# Adafruit_FTDI_Friend_Rev_B.net
KiCad netlist of a schematic drawn in EAGLE
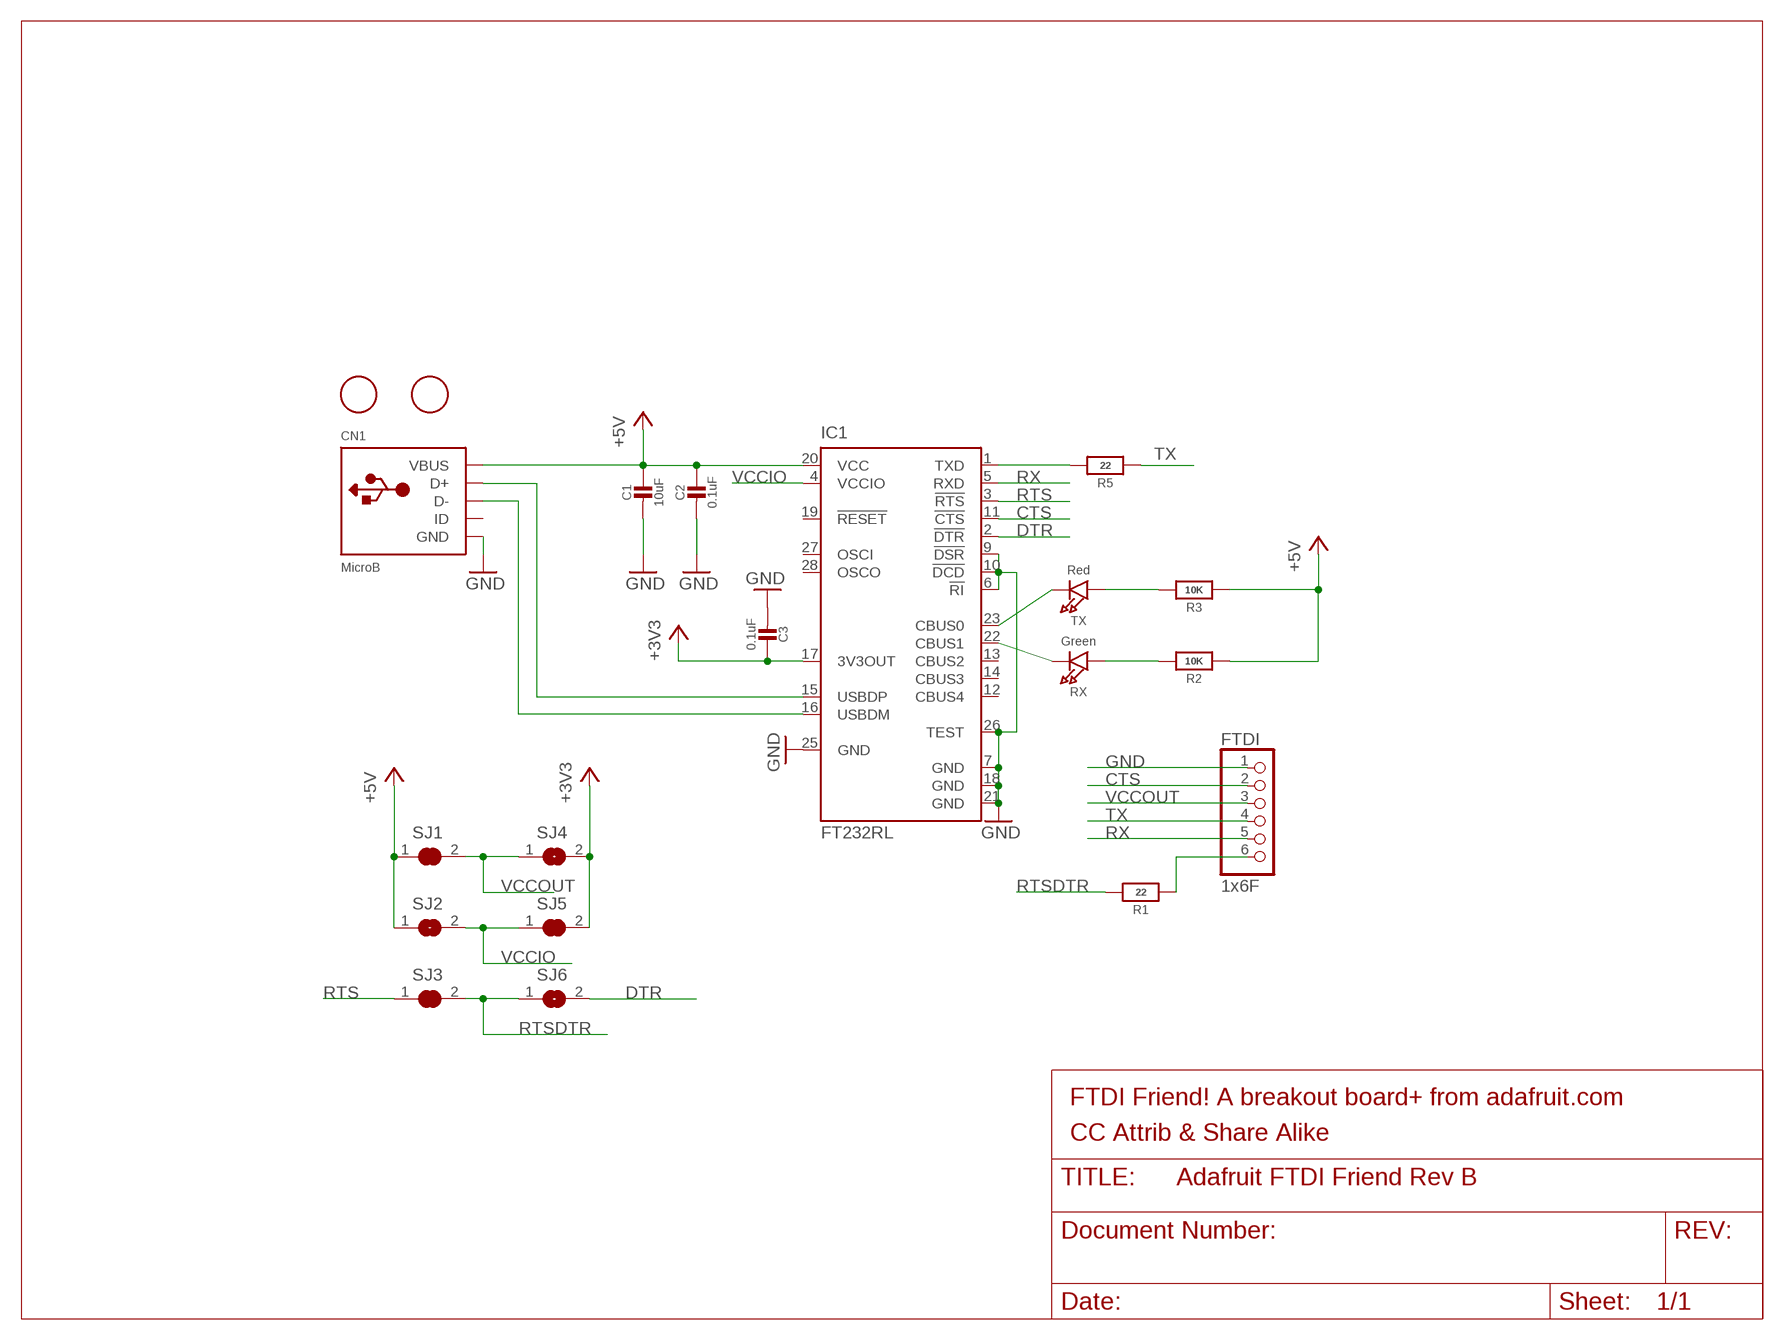
[diagram p0: schematic, sheet 1]

(export (version "E")
  (design (tool "Eeschema 10.0.6"))
  (components
    (comp (ref "C1")
      (value "10uF")
      (footprint "eagle-import:0805-NO")
      (libsource (lib "eagle-import") (part "CAP_CERAMIC0805-NOOUTLINE"))
    )
    (comp (ref "C2")
      (value "0.1uF")
      (footprint "eagle-import:0603-NO")
      (libsource (lib "eagle-import") (part "CAP_CERAMIC0603_NO"))
    )
    (comp (ref "C3")
      (value "0.1uF")
      (footprint "eagle-import:0603-NO")
      (libsource (lib "eagle-import") (part "CAP_CERAMIC0603_NO"))
    )
    (comp (ref "CN1")
      (value "MicroB")
      (footprint "eagle-import:SHOU_MICROXNJ073")
      (libsource (lib "eagle-import") (part "USB_MICROXNJ073"))
    )
    (comp (ref "FTDI")
      (value "1x6F")
      (footprint "eagle-import:1X06-CLEANBIG")
      (libsource (lib "eagle-import") (part "PINHD-1X6CB"))
    )
    (comp (ref "IC1")
      (value "FT232RL")
      (footprint "eagle-import:SSOP28")
      (libsource (lib "eagle-import") (part "FT232RL"))
    )
    (comp (ref "R1")
      (value "22")
      (footprint "eagle-import:0603-NO")
      (libsource (lib "eagle-import") (part "RESISTOR_0603_NOOUT"))
    )
    (comp (ref "R2")
      (value "10K")
      (footprint "eagle-import:0603-NO")
      (libsource (lib "eagle-import") (part "RESISTOR_0603_NOOUT"))
    )
    (comp (ref "R3")
      (value "10K")
      (footprint "eagle-import:0603-NO")
      (libsource (lib "eagle-import") (part "RESISTOR_0603_NOOUT"))
    )
    (comp (ref "R5")
      (value "22")
      (footprint "eagle-import:0603-NO")
      (libsource (lib "eagle-import") (part "RESISTOR_0603_NOOUT"))
    )
    (comp (ref "RX")
      (value "Green")
      (footprint "eagle-import:CHIPLED_0603_NOOUTLINE")
      (libsource (lib "eagle-import") (part "LED0603_NOOUTLINE"))
    )
    (comp (ref "SJ1")
      (value "SOLDERJUMPER_CLOSED")
      (footprint "eagle-import:SOLDERJUMPER_CLOSEDWIRE")
      (libsource (lib "eagle-import") (part "SOLDERJUMPER_CLOSED"))
    )
    (comp (ref "SJ2")
      (value "SOLDERJUMPER")
      (footprint "eagle-import:SOLDERJUMPER_ARROW_NOPASTE")
      (libsource (lib "eagle-import") (part "SOLDERJUMPER"))
    )
    (comp (ref "SJ3")
      (value "SOLDERJUMPER_CLOSED")
      (footprint "eagle-import:SOLDERJUMPER_CLOSEDWIRE")
      (libsource (lib "eagle-import") (part "SOLDERJUMPER_CLOSED"))
    )
    (comp (ref "SJ4")
      (value "SOLDERJUMPER")
      (footprint "eagle-import:SOLDERJUMPER_ARROW_NOPASTE")
      (libsource (lib "eagle-import") (part "SOLDERJUMPER"))
    )
    (comp (ref "SJ5")
      (value "SOLDERJUMPER_CLOSED")
      (footprint "eagle-import:SOLDERJUMPER_CLOSEDWIRE")
      (libsource (lib "eagle-import") (part "SOLDERJUMPER_CLOSED"))
    )
    (comp (ref "SJ6")
      (value "SOLDERJUMPER")
      (footprint "eagle-import:SOLDERJUMPER_ARROW_NOPASTE")
      (libsource (lib "eagle-import") (part "SOLDERJUMPER"))
    )
    (comp (ref "TX")
      (value "Red")
      (footprint "eagle-import:CHIPLED_0603_NOOUTLINE")
      (libsource (lib "eagle-import") (part "LED0603_NOOUTLINE"))
    )
    (comp (ref "U$1")
      (value "FIDUCIAL")
      (footprint "eagle-import:FIDUCIAL_1MM")
      (libsource (lib "eagle-import") (part "FIDUCIAL"))
    )
    (comp (ref "U$2")
      (value "FIDUCIAL")
      (footprint "eagle-import:FIDUCIAL_1MM")
      (libsource (lib "eagle-import") (part "FIDUCIAL"))
    )
  )
  (nets
    (net (code "1") (name "+3V3") (class "Default")
      (node (ref "C3") (pin "1") (pinfunction "1_1") (pintype "passive"))
      (node (ref "IC1") (pin "17") (pinfunction "3V3OUT_17") (pintype "output"))
      (node (ref "SJ4") (pin "2") (pinfunction "2_2") (pintype "passive"))
      (node (ref "SJ5") (pin "2") (pinfunction "2_2") (pintype "passive"))
    )
    (net (code "2") (name "+5V") (class "Default")
      (node (ref "C1") (pin "1") (pinfunction "1_1") (pintype "passive"))
      (node (ref "C2") (pin "1") (pinfunction "1_1") (pintype "passive"))
      (node (ref "CN1") (pin "VBUS") (pinfunction "VBUS_VBUS") (pintype "power_in"))
      (node (ref "IC1") (pin "20") (pinfunction "VCC_20") (pintype "power_in"))
      (node (ref "R2") (pin "1") (pinfunction "1_1") (pintype "passive"))
      (node (ref "R3") (pin "1") (pinfunction "1_1") (pintype "passive"))
      (node (ref "SJ1") (pin "1") (pinfunction "1_1") (pintype "passive"))
      (node (ref "SJ2") (pin "1") (pinfunction "1_1") (pintype "passive"))
    )
    (net (code "3") (name "/CTS") (class "Default")
      (node (ref "FTDI") (pin "2") (pinfunction "2_2") (pintype "passive"))
      (node (ref "IC1") (pin "11") (pinfunction "~{CTS}_11") (pintype "input"))
    )
    (net (code "4") (name "/DTR") (class "Default")
      (node (ref "IC1") (pin "2") (pinfunction "~{DTR}_2") (pintype "output"))
      (node (ref "SJ6") (pin "2") (pinfunction "2_2") (pintype "passive"))
    )
    (net (code "5") (name "/RTS") (class "Default")
      (node (ref "IC1") (pin "3") (pinfunction "~{RTS}_3") (pintype "output"))
      (node (ref "SJ3") (pin "1") (pinfunction "1_1") (pintype "passive"))
    )
    (net (code "6") (name "/RTSDTR") (class "Default")
      (node (ref "R1") (pin "2") (pinfunction "2_2") (pintype "passive"))
      (node (ref "SJ3") (pin "2") (pinfunction "2_2") (pintype "passive"))
      (node (ref "SJ6") (pin "1") (pinfunction "1_1") (pintype "passive"))
    )
    (net (code "7") (name "/RX") (class "Default")
      (node (ref "FTDI") (pin "5") (pinfunction "5_5") (pintype "passive"))
      (node (ref "IC1") (pin "5") (pinfunction "RXD_5") (pintype "input"))
    )
    (net (code "8") (name "/TX") (class "Default")
      (node (ref "FTDI") (pin "4") (pinfunction "4_4") (pintype "passive"))
      (node (ref "R5") (pin "1") (pinfunction "1_1") (pintype "passive"))
    )
    (net (code "9") (name "/VCCIO") (class "Default")
      (node (ref "IC1") (pin "4") (pinfunction "VCCIO_4") (pintype "power_in"))
      (node (ref "SJ2") (pin "2") (pinfunction "2_2") (pintype "passive"))
      (node (ref "SJ5") (pin "1") (pinfunction "1_1") (pintype "passive"))
    )
    (net (code "10") (name "/VCCOUT") (class "Default")
      (node (ref "FTDI") (pin "3") (pinfunction "3_3") (pintype "passive"))
      (node (ref "SJ1") (pin "2") (pinfunction "2_2") (pintype "passive"))
      (node (ref "SJ4") (pin "1") (pinfunction "1_1") (pintype "passive"))
    )
    (net (code "11") (name "GND") (class "Default")
      (node (ref "C1") (pin "2") (pinfunction "2_2") (pintype "passive"))
      (node (ref "C2") (pin "2") (pinfunction "2_2") (pintype "passive"))
      (node (ref "C3") (pin "2") (pinfunction "2_2") (pintype "passive"))
      (node (ref "CN1") (pin "BASE@1") (pinfunction "GND_BASE@1") (pintype "power_in"))
      (node (ref "CN1") (pin "BASE@2") (pinfunction "GND_BASE@2") (pintype "power_in"))
      (node (ref "CN1") (pin "GND") (pinfunction "GND_GND") (pintype "power_in"))
      (node (ref "CN1") (pin "SPRT@1") (pinfunction "GND_SPRT@1") (pintype "power_in"))
      (node (ref "CN1") (pin "SPRT@2") (pinfunction "GND_SPRT@2") (pintype "power_in"))
      (node (ref "CN1") (pin "SPRT@3") (pinfunction "GND_SPRT@3") (pintype "power_in"))
      (node (ref "CN1") (pin "SPRT@4") (pinfunction "GND_SPRT@4") (pintype "power_in"))
      (node (ref "FTDI") (pin "1") (pinfunction "1_1") (pintype "passive"))
      (node (ref "IC1") (pin "10") (pinfunction "~{DCD}_10") (pintype "input"))
      (node (ref "IC1") (pin "18") (pinfunction "GND_18") (pintype "power_in"))
      (node (ref "IC1") (pin "21") (pinfunction "GND_21") (pintype "power_in"))
      (node (ref "IC1") (pin "25") (pinfunction "GND_25") (pintype "power_in"))
      (node (ref "IC1") (pin "26") (pinfunction "TEST_26") (pintype "input"))
      (node (ref "IC1") (pin "6") (pinfunction "~{RI}_6") (pintype "input"))
      (node (ref "IC1") (pin "7") (pinfunction "GND_7") (pintype "power_in"))
      (node (ref "IC1") (pin "9") (pinfunction "~{DSR}_9") (pintype "input"))
    )
    (net (code "12") (name "Net-(FTDI-Pad6)") (class "Default")
      (node (ref "FTDI") (pin "6") (pinfunction "6_6") (pintype "passive"))
      (node (ref "R1") (pin "1") (pinfunction "1_1") (pintype "passive"))
    )
    (net (code "13") (name "Net-(IC1-CBUS0)") (class "Default")
      (node (ref "IC1") (pin "23") (pinfunction "CBUS0_23") (pintype "bidirectional"))
      (node (ref "TX") (pin "C") (pinfunction "C_C") (pintype "passive"))
    )
    (net (code "14") (name "Net-(IC1-CBUS1)") (class "Default")
      (node (ref "IC1") (pin "22") (pinfunction "CBUS1_22") (pintype "bidirectional"))
      (node (ref "RX") (pin "C") (pinfunction "C_C") (pintype "passive"))
    )
    (net (code "15") (name "Net-(IC1-TXD)") (class "Default")
      (node (ref "IC1") (pin "1") (pinfunction "TXD_1") (pintype "output"))
      (node (ref "R5") (pin "2") (pinfunction "2_2") (pintype "passive"))
    )
    (net (code "16") (name "Net-(IC1-USBDM)") (class "Default")
      (node (ref "CN1") (pin "D-") (pinfunction "D-_D-") (pintype "bidirectional"))
      (node (ref "IC1") (pin "16") (pinfunction "USBDM_16") (pintype "bidirectional"))
    )
    (net (code "17") (name "Net-(IC1-USBDP)") (class "Default")
      (node (ref "CN1") (pin "D+") (pinfunction "D+_D+") (pintype "bidirectional"))
      (node (ref "IC1") (pin "15") (pinfunction "USBDP_15") (pintype "bidirectional"))
    )
    (net (code "18") (name "Net-(R2-Pad2)") (class "Default")
      (node (ref "R2") (pin "2") (pinfunction "2_2") (pintype "passive"))
      (node (ref "RX") (pin "A") (pinfunction "A_A") (pintype "passive"))
    )
    (net (code "19") (name "Net-(R3-Pad2)") (class "Default")
      (node (ref "R3") (pin "2") (pinfunction "2_2") (pintype "passive"))
      (node (ref "TX") (pin "A") (pinfunction "A_A") (pintype "passive"))
    )
    (net (code "20") (name "unconnected-(CN1-PadID)") (class "Default")
      (node (ref "CN1") (pin "ID") (pinfunction "ID_ID") (pintype "bidirectional"))
    )
    (net (code "21") (name "unconnected-(IC1-CBUS2-Pad13)") (class "Default")
      (node (ref "IC1") (pin "13") (pinfunction "CBUS2_13") (pintype "bidirectional"))
    )
    (net (code "22") (name "unconnected-(IC1-CBUS3-Pad14)") (class "Default")
      (node (ref "IC1") (pin "14") (pinfunction "CBUS3_14") (pintype "bidirectional"))
    )
    (net (code "23") (name "unconnected-(IC1-CBUS4-Pad12)") (class "Default")
      (node (ref "IC1") (pin "12") (pinfunction "CBUS4_12") (pintype "bidirectional"))
    )
    (net (code "24") (name "unconnected-(IC1-OSCI-Pad27)") (class "Default")
      (node (ref "IC1") (pin "27") (pinfunction "OSCI_27") (pintype "input"))
    )
    (net (code "25") (name "unconnected-(IC1-OSCO-Pad28)") (class "Default")
      (node (ref "IC1") (pin "28") (pinfunction "OSCO_28") (pintype "output"))
    )
    (net (code "26") (name "unconnected-(IC1-~{RESET}-Pad19)") (class "Default")
      (node (ref "IC1") (pin "19") (pinfunction "~{RESET}_19") (pintype "input"))
    )
  )
)
